# Wi_fi_connector.net
KiCad netlist of a schematic drawn in Altium Designer
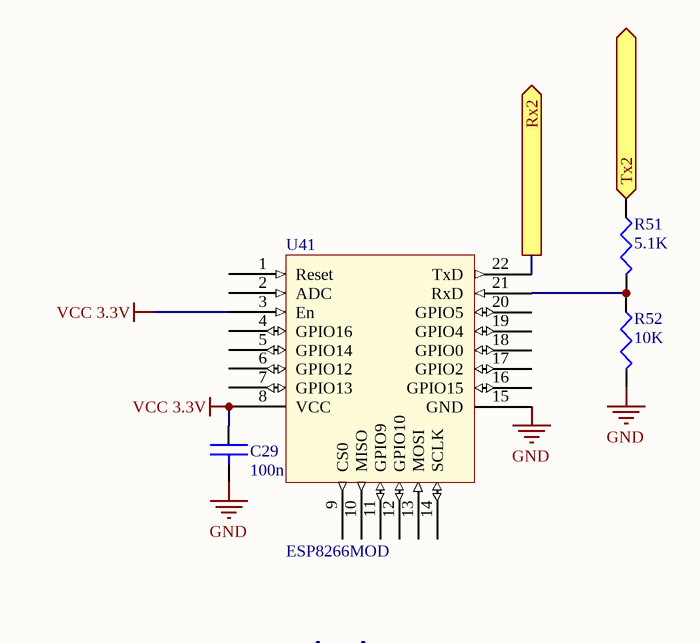
[diagram p0: Wi fi connector.SchDoc]

(export (version "E")
  (design (tool "Eeschema 10.0.6"))
  (components
    (comp (ref "C29")
      (value "100n")
      (footprint "0805")
      (description "capacité non polarisée")
      (fields (field (name "Comment") "CAP"))
      (libsource (lib "ISEN_basics_26-05-2015") (part "CAP"))
    )
    (comp (ref "R51")
      (value "5.1K")
      (footprint "0805")
      (description "resistance")
      (fields (field (name "Comment") "RES"))
      (libsource (lib "ISEN_basics_26-05-2015") (part "RES"))
    )
    (comp (ref "R52")
      (value "10K")
      (footprint "0805")
      (description "resistance")
      (fields (field (name "Comment") "RES"))
      (libsource (lib "ISEN_basics_26-05-2015") (part "RES"))
    )
    (comp (ref "U41")
      (value "ESP8266MOD")
      (footprint "ESP8266MOD Footprint")
      (description "Wi fi ESP")
      (libsource (lib "ESP8266MOD") (part "ESP8266MOD"))
    )
  )
  (nets
    (net (code "1") (name "/Rx2") (class "Default")
      (node (ref "U41") (pin "22") (pinfunction "TxD_22") (pintype "output"))
    )
    (net (code "2") (name "/Tx2") (class "Default") (node (ref "R51") (pin "1") (pintype "passive")))
    (net (code "3") (name "GND") (class "Default")
      (node (ref "C29") (pin "2") (pinfunction "2_2") (pintype "passive"))
      (node (ref "R52") (pin "2") (pintype "passive"))
      (node (ref "U41") (pin "15") (pinfunction "GND_15") (pintype "power_in"))
    )
    (net (code "4") (name "Net-(U41-RxD)") (class "Default")
      (node (ref "R51") (pin "2") (pintype "passive"))
      (node (ref "R52") (pin "1") (pintype "passive"))
      (node (ref "U41") (pin "21") (pinfunction "RxD_21") (pintype "input"))
    )
    (net (code "5") (name "VCC 3.3V") (class "Default")
      (node (ref "C29") (pin "1") (pinfunction "1_1") (pintype "passive"))
      (node (ref "U41") (pin "3") (pinfunction "En_3") (pintype "input"))
      (node (ref "U41") (pin "8") (pinfunction "VCC_8") (pintype "power_in"))
    )
    (net (code "6") (name "unconnected-(U41-ADC-Pad2)") (class "Default")
      (node (ref "U41") (pin "2") (pinfunction "ADC_2") (pintype "input"))
    )
    (net (code "7") (name "unconnected-(U41-CS0-Pad9)") (class "Default")
      (node (ref "U41") (pin "9") (pinfunction "CS0_9") (pintype "output"))
    )
    (net (code "8") (name "unconnected-(U41-GPIO0-Pad18)") (class "Default")
      (node (ref "U41") (pin "18") (pinfunction "GPIO0_18") (pintype "bidirectional"))
    )
    (net (code "9") (name "unconnected-(U41-GPIO2-Pad17)") (class "Default")
      (node (ref "U41") (pin "17") (pinfunction "GPIO2_17") (pintype "bidirectional"))
    )
    (net (code "10") (name "unconnected-(U41-GPIO4-Pad19)") (class "Default")
      (node (ref "U41") (pin "19") (pinfunction "GPIO4_19") (pintype "bidirectional"))
    )
    (net (code "11") (name "unconnected-(U41-GPIO5-Pad20)") (class "Default")
      (node (ref "U41") (pin "20") (pinfunction "GPIO5_20") (pintype "bidirectional"))
    )
    (net (code "12") (name "unconnected-(U41-GPIO9-Pad11)") (class "Default")
      (node (ref "U41") (pin "11") (pinfunction "GPIO9_11") (pintype "bidirectional"))
    )
    (net (code "13") (name "unconnected-(U41-GPIO10-Pad12)") (class "Default")
      (node (ref "U41") (pin "12") (pinfunction "GPIO10_12") (pintype "bidirectional"))
    )
    (net (code "14") (name "unconnected-(U41-GPIO12-Pad6)") (class "Default")
      (node (ref "U41") (pin "6") (pinfunction "GPIO12_6") (pintype "bidirectional"))
    )
    (net (code "15") (name "unconnected-(U41-GPIO13-Pad7)") (class "Default")
      (node (ref "U41") (pin "7") (pinfunction "GPIO13_7") (pintype "bidirectional"))
    )
    (net (code "16") (name "unconnected-(U41-GPIO14-Pad5)") (class "Default")
      (node (ref "U41") (pin "5") (pinfunction "GPIO14_5") (pintype "bidirectional"))
    )
    (net (code "17") (name "unconnected-(U41-GPIO15-Pad16)") (class "Default")
      (node (ref "U41") (pin "16") (pinfunction "GPIO15_16") (pintype "bidirectional"))
    )
    (net (code "18") (name "unconnected-(U41-GPIO16-Pad4)") (class "Default")
      (node (ref "U41") (pin "4") (pinfunction "GPIO16_4") (pintype "bidirectional"))
    )
    (net (code "19") (name "unconnected-(U41-MISO-Pad10)") (class "Default")
      (node (ref "U41") (pin "10") (pinfunction "MISO_10") (pintype "output"))
    )
    (net (code "20") (name "unconnected-(U41-MOSI-Pad13)") (class "Default")
      (node (ref "U41") (pin "13") (pinfunction "MOSI_13") (pintype "input"))
    )
    (net (code "21") (name "unconnected-(U41-Reset-Pad1)") (class "Default")
      (node (ref "U41") (pin "1") (pinfunction "Reset_1") (pintype "input"))
    )
    (net (code "22") (name "unconnected-(U41-SCLK-Pad14)") (class "Default")
      (node (ref "U41") (pin "14") (pinfunction "SCLK_14") (pintype "bidirectional"))
    )
  )
)
